# PX4FMUv2_3_SCH.net
KiCad netlist of a schematic drawn in Altium Designer
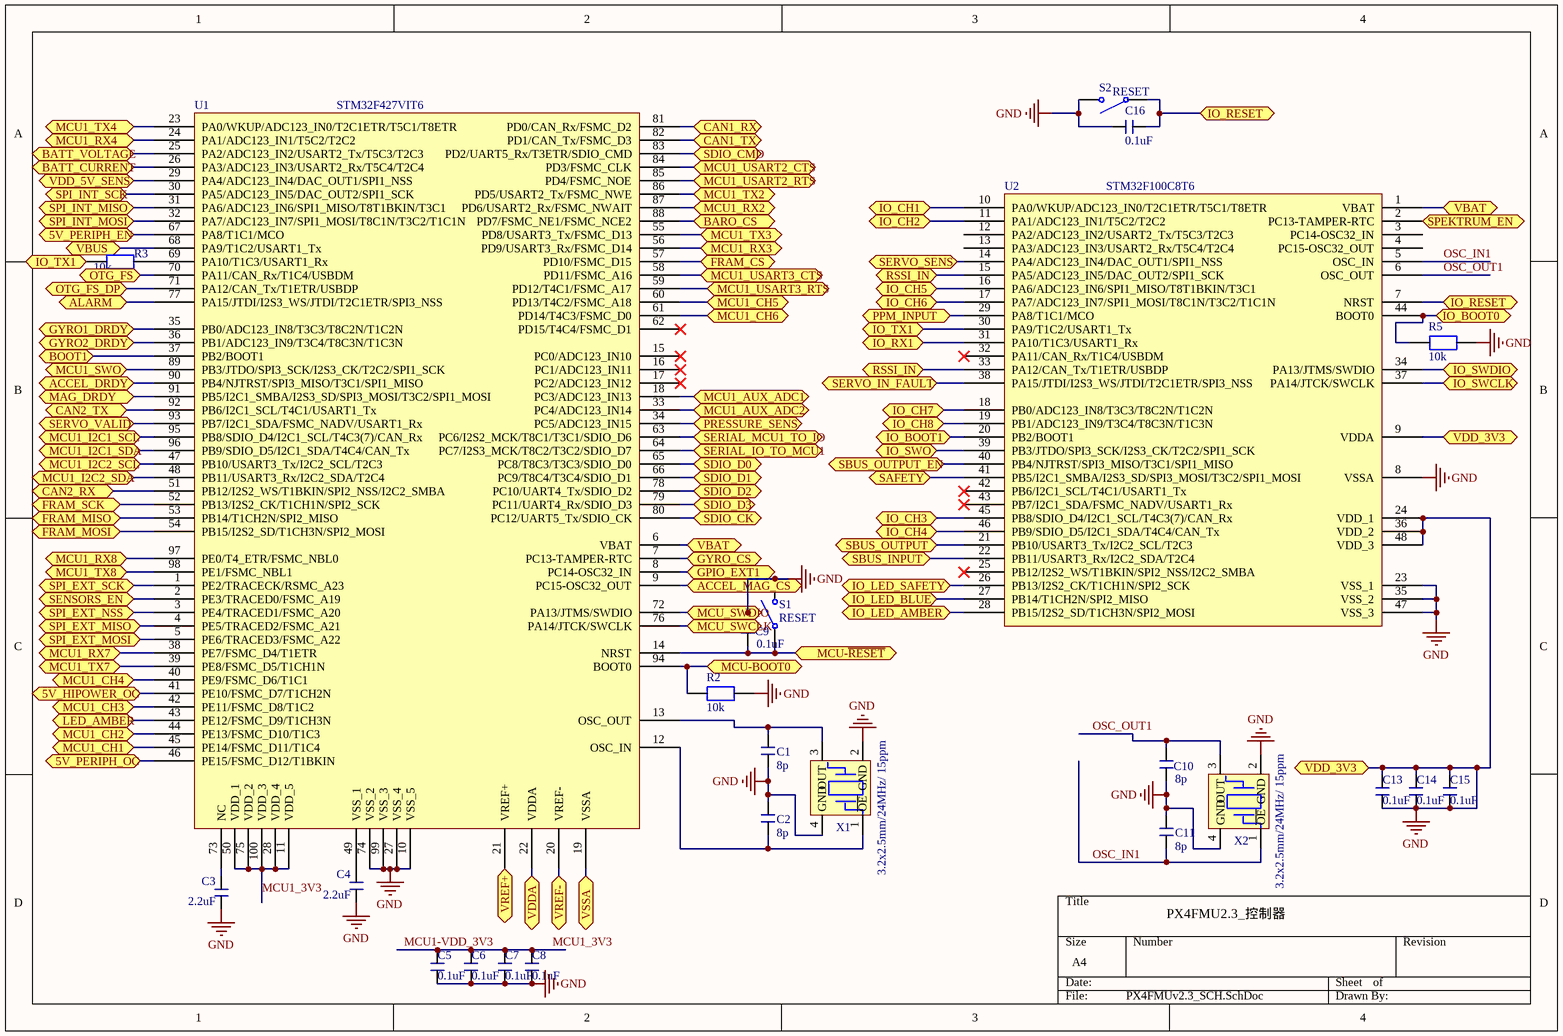
[diagram p0: PX4FMUv2.3_SCH.SchDoc]

(export (version "E")
  (design (tool "Eeschema 10.0.6"))
  (components
    (comp (ref "C1") (value "8p") (footprint "C 0402") (libsource (lib "px4_SCHLIB") (part "CAP_0402")))
    (comp (ref "C2") (value "8p") (footprint "C 0402") (libsource (lib "px4_SCHLIB") (part "CAP_0402")))
    (comp (ref "C3") (value "2.2uF") (footprint "C 0603_L") (libsource (lib "px4_SCHLIB") (part "CAP_0603")))
    (comp (ref "C4") (value "2.2uF") (footprint "C 0603_L") (libsource (lib "px4_SCHLIB") (part "CAP_0603")))
    (comp (ref "C5") (value "0.1uF") (footprint "C 0402") (libsource (lib "px4_SCHLIB") (part "CAP_0402")))
    (comp (ref "C6") (value "0.1uF") (footprint "C 0402") (libsource (lib "px4_SCHLIB") (part "CAP_0402")))
    (comp (ref "C7") (value "0.1uF") (footprint "C 0402") (libsource (lib "px4_SCHLIB") (part "CAP_0402")))
    (comp (ref "C8") (value "0.1uF") (footprint "C 0402") (libsource (lib "px4_SCHLIB") (part "CAP_0402")))
    (comp (ref "C9") (value "0.1uF") (footprint "C 0402") (libsource (lib "px4_SCHLIB") (part "CAP_0402")))
    (comp (ref "C10") (value "8p") (footprint "C 0402") (libsource (lib "px4_SCHLIB") (part "CAP_0402")))
    (comp (ref "C11") (value "8p") (footprint "C 0402") (libsource (lib "px4_SCHLIB") (part "CAP_0402")))
    (comp (ref "C13") (value "0.1uF") (footprint "C 0402") (libsource (lib "px4_SCHLIB") (part "CAP_0402")))
    (comp (ref "C14") (value "0.1uF") (footprint "C 0402") (libsource (lib "px4_SCHLIB") (part "CAP_0402")))
    (comp (ref "C15") (value "0.1uF") (footprint "C 0402") (libsource (lib "px4_SCHLIB") (part "CAP_0402")))
    (comp (ref "C16") (value "0.1uF") (footprint "C 0402") (libsource (lib "px4_SCHLIB") (part "CAP_0402")))
    (comp (ref "R2") (value "10k") (footprint "0402R") (libsource (lib "px4_SCHLIB") (part "Res_0402")))
    (comp (ref "R3") (value "10k") (footprint "0402R") (libsource (lib "px4_SCHLIB") (part "Res_0402")))
    (comp (ref "R5") (value "10k") (footprint "0402R") (libsource (lib "px4_SCHLIB") (part "Res_0402")))
    (comp (ref "S1")
      (value "RESET")
      (footprint "EVQP7J01K")
      (libsource (lib "px4_SCHLIB") (part "SWITCH-MOMENTARY-2"))
    )
    (comp (ref "S2")
      (value "RESET")
      (footprint "EVQP7J01K")
      (libsource (lib "px4_SCHLIB") (part "SWITCH-MOMENTARY-2"))
    )
    (comp (ref "U1")
      (value "STM32F427VIT6")
      (footprint "LQPF_100")
      (libsource (lib "px4_SCHLIB") (part "STM32F427VIT6"))
    )
    (comp (ref "U2")
      (value "STM32F100C8T6")
      (footprint "LQFP_48")
      (libsource (lib "px4_SCHLIB") (part "STM32F100C8T6"))
    )
    (comp (ref "X1")
      (value "3.2x2.5mm/24MHz/ 15ppm")
      (footprint "OSC 3225-4P")
      (libsource (lib "px4_SCHLIB") (part "OSCILLATOR"))
    )
    (comp (ref "X2")
      (value "3.2x2.5mm/24MHz/ 15ppm")
      (footprint "OSC 3225-4P")
      (libsource (lib "px4_SCHLIB") (part "OSCILLATOR"))
    )
  )
  (nets
    (net (code "1") (name "/5V_HIPOWER_OC") (class "Default")
      (node (ref "U1") (pin "41") (pinfunction "PE10/FSMC_D7/T1CH2N_41") (pintype "passive"))
    )
    (net (code "2") (name "/5V_PERIPH_EN") (class "Default")
      (node (ref "U1") (pin "67") (pinfunction "PA8/T1C1/MCO_67") (pintype "passive"))
    )
    (net (code "3") (name "/5V_PERIPH_OC") (class "Default")
      (node (ref "U1") (pin "46") (pinfunction "PE15/FSMC_D12/T1BKIN_46") (pintype "passive"))
    )
    (net (code "4") (name "/ACCEL_DRDY") (class "Default")
      (node (ref "U1") (pin "90") (pinfunction "PB4/NJTRST/SPI3_MISO/T3C1/SPI1_MISO_90") (pintype "passive"))
    )
    (net (code "5") (name "/ACCEL_MAG_CS") (class "Default")
      (node (ref "U1") (pin "9") (pinfunction "PC15-OSC32_OUT_9") (pintype "passive"))
    )
    (net (code "6") (name "/ALARM") (class "Default")
      (node (ref "U1") (pin "77") (pinfunction "PA15/JTDI/I2S3_WS/JTDI/T2C1ETR/SPI3_NSS_77") (pintype "passive"))
    )
    (net (code "7") (name "/BARO_CS") (class "Default")
      (node (ref "U1") (pin "88") (pinfunction "PD7/FSMC_NE1/FSMC_NCE2_88") (pintype "passive"))
    )
    (net (code "8") (name "/BATT_CURRENT") (class "Default")
      (node (ref "U1") (pin "26") (pinfunction "PA3/ADC123_IN3/USART2_Rx/T5C4/T2C4_26") (pintype "passive"))
    )
    (net (code "9") (name "/BATT_VOLTAGE") (class "Default")
      (node (ref "U1") (pin "25") (pinfunction "PA2/ADC123_IN2/USART2_Tx/T5C3/T2C3_25") (pintype "passive"))
    )
    (net (code "10") (name "/BOOT1") (class "Default")
      (node (ref "U1") (pin "37") (pinfunction "PB2/BOOT1_37") (pintype "passive"))
    )
    (net (code "11") (name "/CAN1_RX") (class "Default")
      (node (ref "U1") (pin "81") (pinfunction "PD0/CAN_Rx/FSMC_D2_81") (pintype "passive"))
    )
    (net (code "12") (name "/CAN1_TX") (class "Default")
      (node (ref "U1") (pin "82") (pinfunction "PD1/CAN_Tx/FSMC_D3_82") (pintype "passive"))
    )
    (net (code "13") (name "/CAN2_RX") (class "Default")
      (node (ref "U1") (pin "51") (pinfunction "PB12/I2S2_WS/T1BKIN/SPI2_NSS/I2C2_SMBA_51") (pintype "passive"))
    )
    (net (code "14") (name "/CAN2_TX") (class "Default")
      (node (ref "U1") (pin "92") (pinfunction "PB6/I2C1_SCL/T4C1/USART1_Tx_92") (pintype "passive"))
    )
    (net (code "15") (name "/FRAM_CS") (class "Default")
      (node (ref "U1") (pin "57") (pinfunction "PD10/FSMC_D15_57") (pintype "passive"))
    )
    (net (code "16") (name "/FRAM_MISO") (class "Default")
      (node (ref "U1") (pin "53") (pinfunction "PB14/T1CH2N/SPI2_MISO_53") (pintype "passive"))
    )
    (net (code "17") (name "/FRAM_MOSI") (class "Default")
      (node (ref "U1") (pin "54") (pinfunction "PB15/I2S2_SD/T1CH3N/SPI2_MOSI_54") (pintype "passive"))
    )
    (net (code "18") (name "/FRAM_SCK") (class "Default")
      (node (ref "U1") (pin "52") (pinfunction "PB13/I2S2_CK/T1CH1N/SPI2_SCK_52") (pintype "passive"))
    )
    (net (code "19") (name "/GPIO_EXT1") (class "Default")
      (node (ref "U1") (pin "8") (pinfunction "PC14-OSC32_IN_8") (pintype "passive"))
    )
    (net (code "20") (name "/GYRO1_DRDY") (class "Default")
      (node (ref "U1") (pin "35") (pinfunction "PB0/ADC123_IN8/T3C3/T8C2N/T1C2N_35") (pintype "passive"))
    )
    (net (code "21") (name "/GYRO2_DRDY") (class "Default")
      (node (ref "U1") (pin "36") (pinfunction "PB1/ADC123_IN9/T3C4/T8C3N/T1C3N_36") (pintype "passive"))
    )
    (net (code "22") (name "/GYRO_CS") (class "Default")
      (node (ref "U1") (pin "7") (pinfunction "PC13-TAMPER-RTC_7") (pintype "passive"))
    )
    (net (code "23") (name "/IO_BOOT0") (class "Default")
      (node (ref "R5") (pin "2") (pinfunction "2_2") (pintype "passive"))
      (node (ref "U2") (pin "44") (pinfunction "BOOT0_44") (pintype "passive"))
    )
    (net (code "24") (name "/IO_BOOT1") (class "Default")
      (node (ref "U2") (pin "20") (pinfunction "PB2/BOOT1_20") (pintype "passive"))
    )
    (net (code "25") (name "/IO_CH1") (class "Default")
      (node (ref "U2") (pin "10") (pinfunction "PA0/WKUP/ADC123_IN0/T2C1ETR/T5C1/T8ETR_10") (pintype "passive"))
    )
    (net (code "26") (name "/IO_CH2") (class "Default")
      (node (ref "U2") (pin "11") (pinfunction "PA1/ADC123_IN1/T5C2/T2C2_11") (pintype "passive"))
    )
    (net (code "27") (name "/IO_CH3") (class "Default")
      (node (ref "U2") (pin "45") (pinfunction "PB8/SDIO_D4/I2C1_SCL/T4C3(7)/CAN_Rx_45") (pintype "passive"))
    )
    (net (code "28") (name "/IO_CH4") (class "Default")
      (node (ref "U2") (pin "46") (pinfunction "PB9/SDIO_D5/I2C1_SDA/T4C4/CAN_Tx_46") (pintype "passive"))
    )
    (net (code "29") (name "/IO_CH5") (class "Default")
      (node (ref "U2") (pin "16") (pinfunction "PA6/ADC123_IN6/SPI1_MISO/T8T1BKIN/T3C1_16") (pintype "passive"))
    )
    (net (code "30") (name "/IO_CH6") (class "Default")
      (node (ref "U2") (pin "17") (pinfunction "PA7/ADC123_IN7/SPI1_MOSI/T8C1N/T3C2/T1C1N_17") (pintype "passive"))
    )
    (net (code "31") (name "/IO_CH7") (class "Default")
      (node (ref "U2") (pin "18") (pinfunction "PB0/ADC123_IN8/T3C3/T8C2N/T1C2N_18") (pintype "passive"))
    )
    (net (code "32") (name "/IO_CH8") (class "Default")
      (node (ref "U2") (pin "19") (pinfunction "PB1/ADC123_IN9/T3C4/T8C3N/T1C3N_19") (pintype "passive"))
    )
    (net (code "33") (name "/IO_LED_AMBER") (class "Default")
      (node (ref "U2") (pin "28") (pinfunction "PB15/I2S2_SD/T1CH3N/SPI2_MOSI_28") (pintype "passive"))
    )
    (net (code "34") (name "/IO_LED_BLUE") (class "Default")
      (node (ref "U2") (pin "27") (pinfunction "PB14/T1CH2N/SPI2_MISO_27") (pintype "passive"))
    )
    (net (code "35") (name "/IO_LED_SAFETY") (class "Default")
      (node (ref "U2") (pin "26") (pinfunction "PB13/I2S2_CK/T1CH1N/SPI2_SCK_26") (pintype "passive"))
    )
    (net (code "36") (name "/IO_RESET") (class "Default")
      (node (ref "C16") (pin "1") (pinfunction "1_1") (pintype "passive"))
      (node (ref "S2") (pin "1") (pinfunction "1_1") (pintype "passive"))
      (node (ref "U2") (pin "7") (pinfunction "NRST_7") (pintype "passive"))
    )
    (net (code "37") (name "/IO_RX1") (class "Default")
      (node (ref "U2") (pin "31") (pinfunction "PA10/T1C3/USART1_Rx_31") (pintype "passive"))
    )
    (net (code "38") (name "/IO_SWCLK") (class "Default")
      (node (ref "U2") (pin "37") (pinfunction "PA14/JTCK/SWCLK_37") (pintype "passive"))
    )
    (net (code "39") (name "/IO_SWDIO") (class "Default")
      (node (ref "U2") (pin "34") (pinfunction "PA13/JTMS/SWDIO_34") (pintype "passive"))
    )
    (net (code "40") (name "/IO_SWO") (class "Default")
      (node (ref "U2") (pin "39") (pinfunction "PB3/JTDO/SPI3_SCK/I2S3_CK/T2C2/SPI1_SCK_39") (pintype "passive"))
    )
    (net (code "41") (name "/IO_TX1") (class "Default")
      (node (ref "R3") (pin "1") (pinfunction "1_1") (pintype "passive"))
      (node (ref "U2") (pin "30") (pinfunction "PA9/T1C2/USART1_Tx_30") (pintype "passive"))
    )
    (net (code "42") (name "/LED_AMBER") (class "Default")
      (node (ref "U1") (pin "43") (pinfunction "PE12/FSMC_D9/T1CH3N_43") (pintype "passive"))
    )
    (net (code "43") (name "/MAG_DRDY") (class "Default")
      (node (ref "U1") (pin "91") (pinfunction "PB5/I2C1_SMBA/I2S3_SD/SPI3_MOSI/T3C2/SPI1_MOSI_91") (pintype "passive"))
    )
    (net (code "44") (name "/MCU-BOOT0") (class "Default")
      (node (ref "R2") (pin "2") (pinfunction "2_2") (pintype "passive"))
      (node (ref "U1") (pin "94") (pinfunction "BOOT0_94") (pintype "passive"))
    )
    (net (code "45") (name "/MCU-~{RESET}") (class "Default")
      (node (ref "C9") (pin "1") (pinfunction "1_1") (pintype "passive"))
      (node (ref "S1") (pin "1") (pinfunction "1_1") (pintype "passive"))
      (node (ref "U1") (pin "14") (pinfunction "NRST_14") (pintype "passive"))
    )
    (net (code "46") (name "/MCU1-VDD_3V3") (class "Default")
      (node (ref "C5") (pin "1") (pinfunction "1_1") (pintype "passive"))
      (node (ref "C6") (pin "1") (pinfunction "1_1") (pintype "passive"))
      (node (ref "C7") (pin "1") (pinfunction "1_1") (pintype "passive"))
      (node (ref "C8") (pin "1") (pinfunction "1_1") (pintype "passive"))
      (node (ref "U1") (pin "100") (pinfunction "VDD_3_100") (pintype "passive"))
      (node (ref "U1") (pin "11") (pinfunction "VDD_5_11") (pintype "passive"))
      (node (ref "U1") (pin "28") (pinfunction "VDD_4_28") (pintype "passive"))
      (node (ref "U1") (pin "50") (pinfunction "VDD_1_50") (pintype "passive"))
      (node (ref "U1") (pin "75") (pinfunction "VDD_2_75") (pintype "passive"))
    )
    (net (code "47") (name "/MCU1_AUX_ADC1") (class "Default")
      (node (ref "U1") (pin "18") (pinfunction "PC3/ADC123_IN13_18") (pintype "passive"))
    )
    (net (code "48") (name "/MCU1_AUX_ADC2") (class "Default")
      (node (ref "U1") (pin "33") (pinfunction "PC4/ADC123_IN14_33") (pintype "passive"))
    )
    (net (code "49") (name "/MCU1_CH1") (class "Default")
      (node (ref "U1") (pin "45") (pinfunction "PE14/FSMC_D11/T1C4_45") (pintype "passive"))
    )
    (net (code "50") (name "/MCU1_CH2") (class "Default")
      (node (ref "U1") (pin "44") (pinfunction "PE13/FSMC_D10/T1C3_44") (pintype "passive"))
    )
    (net (code "51") (name "/MCU1_CH3") (class "Default")
      (node (ref "U1") (pin "42") (pinfunction "PE11/FSMC_D8/T1C2_42") (pintype "passive"))
    )
    (net (code "52") (name "/MCU1_CH4") (class "Default")
      (node (ref "U1") (pin "40") (pinfunction "PE9/FSMC_D6/T1C1_40") (pintype "passive"))
    )
    (net (code "53") (name "/MCU1_CH5") (class "Default")
      (node (ref "U1") (pin "60") (pinfunction "PD13/T4C2/FSMC_A18_60") (pintype "passive"))
    )
    (net (code "54") (name "/MCU1_CH6") (class "Default")
      (node (ref "U1") (pin "61") (pinfunction "PD14/T4C3/FSMC_D0_61") (pintype "passive"))
    )
    (net (code "55") (name "/MCU1_I2C1_SCL") (class "Default")
      (node (ref "U1") (pin "95") (pinfunction "PB8/SDIO_D4/I2C1_SCL/T4C3(7)/CAN_Rx_95") (pintype "passive"))
    )
    (net (code "56") (name "/MCU1_I2C1_SDA") (class "Default")
      (node (ref "U1") (pin "96") (pinfunction "PB9/SDIO_D5/I2C1_SDA/T4C4/CAN_Tx_96") (pintype "passive"))
    )
    (net (code "57") (name "/MCU1_I2C2_SCL") (class "Default")
      (node (ref "U1") (pin "47") (pinfunction "PB10/USART3_Tx/I2C2_SCL/T2C3_47") (pintype "passive"))
    )
    (net (code "58") (name "/MCU1_I2C2_SDA") (class "Default")
      (node (ref "U1") (pin "48") (pinfunction "PB11/USART3_Rx/I2C2_SDA/T2C4_48") (pintype "passive"))
    )
    (net (code "59") (name "/MCU1_RX2") (class "Default")
      (node (ref "U1") (pin "87") (pinfunction "PD6/USART2_Rx/FSMC_NWAIT_87") (pintype "passive"))
    )
    (net (code "60") (name "/MCU1_RX3") (class "Default")
      (node (ref "U1") (pin "56") (pinfunction "PD9/USART3_Rx/FSMC_D14_56") (pintype "passive"))
    )
    (net (code "61") (name "/MCU1_RX4") (class "Default")
      (node (ref "U1") (pin "24") (pinfunction "PA1/ADC123_IN1/T5C2/T2C2_24") (pintype "passive"))
    )
    (net (code "62") (name "/MCU1_RX7") (class "Default")
      (node (ref "U1") (pin "38") (pinfunction "PE7/FSMC_D4/T1ETR_38") (pintype "passive"))
    )
    (net (code "63") (name "/MCU1_RX8") (class "Default")
      (node (ref "U1") (pin "97") (pinfunction "PE0/T4_ETR/FSMC_NBL0_97") (pintype "passive"))
    )
    (net (code "64") (name "/MCU1_SWO") (class "Default")
      (node (ref "U1") (pin "89") (pinfunction "PB3/JTDO/SPI3_SCK/I2S3_CK/T2C2/SPI1_SCK_89") (pintype "passive"))
    )
    (net (code "65") (name "/MCU1_TX2") (class "Default")
      (node (ref "U1") (pin "86") (pinfunction "PD5/USART2_Tx/FSMC_NWE_86") (pintype "passive"))
    )
    (net (code "66") (name "/MCU1_TX3") (class "Default")
      (node (ref "U1") (pin "55") (pinfunction "PD8/USART3_Tx/FSMC_D13_55") (pintype "passive"))
    )
    (net (code "67") (name "/MCU1_TX4") (class "Default")
      (node (ref "U1") (pin "23") (pinfunction "PA0/WKUP/ADC123_IN0/T2C1ETR/T5C1/T8ETR_23") (pintype "passive"))
    )
    (net (code "68") (name "/MCU1_TX7") (class "Default")
      (node (ref "U1") (pin "39") (pinfunction "PE8/FSMC_D5/T1CH1N_39") (pintype "passive"))
    )
    (net (code "69") (name "/MCU1_TX8") (class "Default")
      (node (ref "U1") (pin "98") (pinfunction "PE1/FSMC_NBL1_98") (pintype "passive"))
    )
    (net (code "70") (name "/MCU1_USART2_CTS") (class "Default")
      (node (ref "U1") (pin "84") (pinfunction "PD3/FSMC_CLK_84") (pintype "passive"))
    )
    (net (code "71") (name "/MCU1_USART2_RTS") (class "Default")
      (node (ref "U1") (pin "85") (pinfunction "PD4/FSMC_NOE_85") (pintype "passive"))
    )
    (net (code "72") (name "/MCU1_USART3_CTS") (class "Default")
      (node (ref "U1") (pin "58") (pinfunction "PD11/FSMC_A16_58") (pintype "passive"))
    )
    (net (code "73") (name "/MCU1_USART3_RTS") (class "Default")
      (node (ref "U1") (pin "59") (pinfunction "PD12/T4C1/FSMC_A17_59") (pintype "passive"))
    )
    (net (code "74") (name "/MCU_SWCLK") (class "Default")
      (node (ref "U1") (pin "76") (pinfunction "PA14/JTCK/SWCLK_76") (pintype "passive"))
    )
    (net (code "75") (name "/MCU_SWDIO") (class "Default")
      (node (ref "U1") (pin "72") (pinfunction "PA13/JTMS/SWDIO_72") (pintype "passive"))
    )
    (net (code "76") (name "/OSC_IN1") (class "Default")
      (node (ref "C11") (pin "2") (pinfunction "2_2") (pintype "passive"))
      (node (ref "U2") (pin "5") (pinfunction "OSC_IN_5") (pintype "passive"))
      (node (ref "X2") (pin "1") (pinfunction "OE_1") (pintype "passive"))
    )
    (net (code "77") (name "/OSC_OUT1") (class "Default")
      (node (ref "C10") (pin "1") (pinfunction "1_1") (pintype "passive"))
      (node (ref "U2") (pin "6") (pinfunction "OSC_OUT_6") (pintype "passive"))
      (node (ref "X2") (pin "3") (pinfunction "OUT_3") (pintype "passive"))
    )
    (net (code "78") (name "/OTG_FS") (class "Default")
      (node (ref "U1") (pin "70") (pinfunction "PA11/CAN_Rx/T1C4/USBDM_70") (pintype "passive"))
    )
    (net (code "79") (name "/OTG_FS_DP") (class "Default")
      (node (ref "U1") (pin "71") (pinfunction "PA12/CAN_Tx/T1ETR/USBDP_71") (pintype "passive"))
    )
    (net (code "80") (name "/PPM_INPUT") (class "Default")
      (node (ref "U2") (pin "29") (pinfunction "PA8/T1C1/MCO_29") (pintype "passive"))
    )
    (net (code "81") (name "/PRESSURE_SENS") (class "Default")
      (node (ref "U1") (pin "34") (pinfunction "PC5/ADC123_IN15_34") (pintype "passive"))
    )
    (net (code "82") (name "/RSSI_IN") (class "Default")
      (node (ref "U2") (pin "15") (pinfunction "PA5/ADC123_IN5/DAC_OUT2/SPI1_SCK_15") (pintype "passive"))
      (node (ref "U2") (pin "33") (pinfunction "PA12/CAN_Tx/T1ETR/USBDP_33") (pintype "passive"))
    )
    (net (code "83") (name "/SAFETY") (class "Default")
      (node (ref "U2") (pin "41") (pinfunction "PB5/I2C1_SMBA/I2S3_SD/SPI3_MOSI/T3C2/SPI1_MOSI_41") (pintype "passive"))
    )
    (net (code "84") (name "/SBUS_INPUT") (class "Default")
      (node (ref "U2") (pin "22") (pinfunction "PB11/USART3_Rx/I2C2_SDA/T2C4_22") (pintype "passive"))
    )
    (net (code "85") (name "/SBUS_OUTPUT") (class "Default")
      (node (ref "U2") (pin "21") (pinfunction "PB10/USART3_Tx/I2C2_SCL/T2C3_21") (pintype "passive"))
    )
    (net (code "86") (name "/SBUS_OUTPUT_EN") (class "Default")
      (node (ref "U2") (pin "40") (pinfunction "PB4/NJTRST/SPI3_MISO/T3C1/SPI1_MISO_40") (pintype "passive"))
    )
    (net (code "87") (name "/SDIO_CK") (class "Default")
      (node (ref "U1") (pin "80") (pinfunction "PC12/UART5_Tx/SDIO_CK_80") (pintype "passive"))
    )
    (net (code "88") (name "/SDIO_CMD") (class "Default")
      (node (ref "U1") (pin "83") (pinfunction "PD2/UART5_Rx/T3ETR/SDIO_CMD_83") (pintype "passive"))
    )
    (net (code "89") (name "/SDIO_D0") (class "Default")
      (node (ref "U1") (pin "65") (pinfunction "PC8/T8C3/T3C3/SDIO_D0_65") (pintype "passive"))
    )
    (net (code "90") (name "/SDIO_D1") (class "Default")
      (node (ref "U1") (pin "66") (pinfunction "PC9/T8C4/T3C4/SDIO_D1_66") (pintype "passive"))
    )
    (net (code "91") (name "/SDIO_D2") (class "Default")
      (node (ref "U1") (pin "78") (pinfunction "PC10/UART4_Tx/SDIO_D2_78") (pintype "passive"))
    )
    (net (code "92") (name "/SDIO_D3") (class "Default")
      (node (ref "U1") (pin "79") (pinfunction "PC11/UART4_Rx/SDIO_D3_79") (pintype "passive"))
    )
    (net (code "93") (name "/SENSORS_EN") (class "Default")
      (node (ref "U1") (pin "2") (pinfunction "PE3/TRACED0/FSMC_A19_2") (pintype "passive"))
    )
    (net (code "94") (name "/SERIAL_IO_TO_MCU1") (class "Default")
      (node (ref "U1") (pin "64") (pinfunction "PC7/I2S3_MCK/T8C2/T3C2/SDIO_D7_64") (pintype "passive"))
    )
    (net (code "95") (name "/SERIAL_MCU1_TO_IO") (class "Default")
      (node (ref "U1") (pin "63") (pinfunction "PC6/I2S2_MCK/T8C1/T3C1/SDIO_D6_63") (pintype "passive"))
    )
    (net (code "96") (name "/SERVO_IN_FAULT") (class "Default")
      (node (ref "U2") (pin "38") (pinfunction "PA15/JTDI/I2S3_WS/JTDI/T2C1ETR/SPI3_NSS_38") (pintype "passive"))
    )
    (net (code "97") (name "/SERVO_SENS") (class "Default")
      (node (ref "U2") (pin "14") (pinfunction "PA4/ADC123_IN4/DAC_OUT1/SPI1_NSS_14") (pintype "passive"))
    )
    (net (code "98") (name "/SERVO_VALID") (class "Default")
      (node (ref "U1") (pin "93") (pinfunction "PB7/I2C1_SDA/FSMC_NADV/USART1_Rx_93") (pintype "passive"))
    )
    (net (code "99") (name "/SPEKTRUM_EN") (class "Default")
      (node (ref "U2") (pin "2") (pinfunction "PC13-TAMPER-RTC_2") (pintype "passive"))
    )
    (net (code "100") (name "/SPI_EXT_MISO") (class "Default")
      (node (ref "U1") (pin "4") (pinfunction "PE5/TRACED2/FSMC_A21_4") (pintype "passive"))
    )
    (net (code "101") (name "/SPI_EXT_MOSI") (class "Default")
      (node (ref "U1") (pin "5") (pinfunction "PE6/TRACED3/FSMC_A22_5") (pintype "passive"))
    )
    (net (code "102") (name "/SPI_EXT_NSS") (class "Default")
      (node (ref "U1") (pin "3") (pinfunction "PE4/TRACED1/FSMC_A20_3") (pintype "passive"))
    )
    (net (code "103") (name "/SPI_EXT_SCK") (class "Default")
      (node (ref "U1") (pin "1") (pinfunction "PE2/TRACECK/RSMC_A23_1") (pintype "passive"))
    )
    (net (code "104") (name "/SPI_INT_MISO") (class "Default")
      (node (ref "U1") (pin "31") (pinfunction "PA6/ADC123_IN6/SPI1_MISO/T8T1BKIN/T3C1_31") (pintype "passive"))
    )
    (net (code "105") (name "/SPI_INT_MOSI") (class "Default")
      (node (ref "U1") (pin "32") (pinfunction "PA7/ADC123_IN7/SPI1_MOSI/T8C1N/T3C2/T1C1N_32") (pintype "passive"))
    )
    (net (code "106") (name "/SPI_INT_SCK") (class "Default")
      (node (ref "U1") (pin "30") (pinfunction "PA5/ADC123_IN5/DAC_OUT2/SPI1_SCK_30") (pintype "passive"))
    )
    (net (code "107") (name "/VBAT") (class "Default")
      (node (ref "U1") (pin "6") (pinfunction "VBAT_6") (pintype "passive"))
      (node (ref "U2") (pin "1") (pinfunction "VBAT_1") (pintype "passive"))
    )
    (net (code "108") (name "/VBUS") (class "Default")
      (node (ref "U1") (pin "68") (pinfunction "PA9/T1C2/USART1_Tx_68") (pintype "passive"))
    )
    (net (code "109") (name "/VDDA") (class "Default")
      (node (ref "U1") (pin "22") (pinfunction "VDDA_22") (pintype "passive"))
    )
    (net (code "110") (name "/VDD_5V_SENS") (class "Default")
      (node (ref "U1") (pin "29") (pinfunction "PA4/ADC123_IN4/DAC_OUT1/SPI1_NSS_29") (pintype "passive"))
    )
    (net (code "111") (name "/VREF+") (class "Default")
      (node (ref "U1") (pin "21") (pinfunction "VREF+_21") (pintype "passive"))
    )
    (net (code "112") (name "/VREF-") (class "Default")
      (node (ref "U1") (pin "20") (pinfunction "VREF-_20") (pintype "passive"))
    )
    (net (code "113") (name "/VSSA") (class "Default")
      (node (ref "U1") (pin "19") (pinfunction "VSSA_19") (pintype "passive"))
    )
    (net (code "114") (name "GND") (class "Default")
      (node (ref "C1") (pin "2") (pinfunction "2_2") (pintype "passive"))
      (node (ref "C10") (pin "2") (pinfunction "2_2") (pintype "passive"))
      (node (ref "C11") (pin "1") (pinfunction "1_1") (pintype "passive"))
      (node (ref "C13") (pin "1") (pinfunction "1_1") (pintype "passive"))
      (node (ref "C13") (pin "2") (pinfunction "2_2") (pintype "passive"))
      (node (ref "C14") (pin "1") (pinfunction "1_1") (pintype "passive"))
      (node (ref "C14") (pin "2") (pinfunction "2_2") (pintype "passive"))
      (node (ref "C15") (pin "1") (pinfunction "1_1") (pintype "passive"))
      (node (ref "C15") (pin "2") (pinfunction "2_2") (pintype "passive"))
      (node (ref "C16") (pin "2") (pinfunction "2_2") (pintype "passive"))
      (node (ref "C2") (pin "1") (pinfunction "1_1") (pintype "passive"))
      (node (ref "C3") (pin "2") (pinfunction "2_2") (pintype "passive"))
      (node (ref "C4") (pin "2") (pinfunction "2_2") (pintype "passive"))
      (node (ref "C5") (pin "2") (pinfunction "2_2") (pintype "passive"))
      (node (ref "C6") (pin "2") (pinfunction "2_2") (pintype "passive"))
      (node (ref "C7") (pin "2") (pinfunction "2_2") (pintype "passive"))
      (node (ref "C8") (pin "2") (pinfunction "2_2") (pintype "passive"))
      (node (ref "C9") (pin "2") (pinfunction "2_2") (pintype "passive"))
      (node (ref "R2") (pin "1") (pinfunction "1_1") (pintype "passive"))
      (node (ref "R5") (pin "1") (pinfunction "1_1") (pintype "passive"))
      (node (ref "S1") (pin "2") (pinfunction "2_2") (pintype "passive"))
      (node (ref "S2") (pin "2") (pinfunction "2_2") (pintype "passive"))
      (node (ref "U1") (pin "10") (pinfunction "VSS_5_10") (pintype "passive"))
      (node (ref "U1") (pin "27") (pinfunction "VSS_4_27") (pintype "passive"))
      (node (ref "U1") (pin "74") (pinfunction "VSS_2_74") (pintype "passive"))
      (node (ref "U1") (pin "99") (pinfunction "VSS_3_99") (pintype "passive"))
      (node (ref "U2") (pin "23") (pinfunction "VSS_1_23") (pintype "passive"))
      (node (ref "U2") (pin "24") (pinfunction "VDD_1_24") (pintype "passive"))
      (node (ref "U2") (pin "35") (pinfunction "VSS_2_35") (pintype "passive"))
      (node (ref "U2") (pin "36") (pinfunction "VDD_2_36") (pintype "passive"))
      (node (ref "U2") (pin "47") (pinfunction "VSS_3_47") (pintype "passive"))
      (node (ref "U2") (pin "48") (pinfunction "VDD_3_48") (pintype "passive"))
      (node (ref "U2") (pin "8") (pinfunction "VSSA_8") (pintype "passive"))
      (node (ref "U2") (pin "9") (pinfunction "VDDA_9") (pintype "passive"))
      (node (ref "X1") (pin "2") (pinfunction "GND_2") (pintype "passive"))
      (node (ref "X1") (pin "4") (pinfunction "GND_4") (pintype "passive"))
      (node (ref "X2") (pin "2") (pinfunction "GND_2") (pintype "passive"))
      (node (ref "X2") (pin "4") (pinfunction "GND_4") (pintype "passive"))
    )
    (net (code "115") (name "Net-(U1-NC)") (class "Default")
      (node (ref "C3") (pin "1") (pinfunction "1_1") (pintype "passive"))
      (node (ref "U1") (pin "73") (pinfunction "NC_73") (pintype "passive"))
    )
    (net (code "116") (name "Net-(U1-OSC_IN)") (class "Default")
      (node (ref "C2") (pin "2") (pinfunction "2_2") (pintype "passive"))
      (node (ref "U1") (pin "12") (pinfunction "OSC_IN_12") (pintype "passive"))
      (node (ref "X1") (pin "1") (pinfunction "OE_1") (pintype "passive"))
    )
    (net (code "117") (name "Net-(U1-OSC_OUT)") (class "Default")
      (node (ref "C1") (pin "1") (pinfunction "1_1") (pintype "passive"))
      (node (ref "U1") (pin "13") (pinfunction "OSC_OUT_13") (pintype "passive"))
      (node (ref "X1") (pin "3") (pinfunction "OUT_3") (pintype "passive"))
    )
    (net (code "118") (name "Net-(U1-PA10{slash}T1C3{slash}USART1_Rx)") (class "Default")
      (node (ref "R3") (pin "2") (pinfunction "2_2") (pintype "passive"))
      (node (ref "U1") (pin "69") (pinfunction "PA10/T1C3/USART1_Rx_69") (pintype "passive"))
    )
    (net (code "119") (name "Net-(U1-VSS_1)") (class "Default")
      (node (ref "C4") (pin "1") (pinfunction "1_1") (pintype "passive"))
      (node (ref "U1") (pin "49") (pinfunction "VSS_1_49") (pintype "passive"))
    )
    (net (code "120") (name "unconnected-(U1-PC0{slash}ADC123_IN10-Pad15)") (class "Default")
      (node (ref "U1") (pin "15") (pinfunction "PC0/ADC123_IN10_15") (pintype "passive+no_connect"))
    )
    (net (code "121") (name "unconnected-(U1-PC1{slash}ADC123_IN11-Pad16)") (class "Default")
      (node (ref "U1") (pin "16") (pinfunction "PC1/ADC123_IN11_16") (pintype "passive+no_connect"))
    )
    (net (code "122") (name "unconnected-(U1-PC2{slash}ADC123_IN12-Pad17)") (class "Default")
      (node (ref "U1") (pin "17") (pinfunction "PC2/ADC123_IN12_17") (pintype "passive+no_connect"))
    )
    (net (code "123") (name "unconnected-(U1-PD15{slash}T4C4{slash}FSMC_D1-Pad62)") (class "Default")
      (node (ref "U1") (pin "62") (pinfunction "PD15/T4C4/FSMC_D1_62") (pintype "passive+no_connect"))
    )
    (net (code "124") (name "unconnected-(U2-PA2{slash}ADC123_IN2{slash}USART2_Tx{slash}T5C3{slash}T2C3-Pad12)") (class "Default")
      (node (ref "U2") (pin "12") (pinfunction "PA2/ADC123_IN2/USART2_Tx/T5C3/T2C3_12") (pintype "passive"))
    )
    (net (code "125") (name "unconnected-(U2-PA3{slash}ADC123_IN3{slash}USART2_Rx{slash}T5C4{slash}T2C4-Pad13)") (class "Default")
      (node (ref "U2") (pin "13") (pinfunction "PA3/ADC123_IN3/USART2_Rx/T5C4/T2C4_13") (pintype "passive"))
    )
    (net (code "126") (name "unconnected-(U2-PA11{slash}CAN_Rx{slash}T1C4{slash}USBDM-Pad32)") (class "Default")
      (node (ref "U2") (pin "32") (pinfunction "PA11/CAN_Rx/T1C4/USBDM_32") (pintype "passive+no_connect"))
    )
    (net (code "127") (name "unconnected-(U2-PB6{slash}I2C1_SCL{slash}T4C1{slash}USART1_Tx-Pad42)") (class "Default")
      (node (ref "U2") (pin "42") (pinfunction "PB6/I2C1_SCL/T4C1/USART1_Tx_42") (pintype "passive+no_connect"))
    )
    (net (code "128") (name "unconnected-(U2-PB7{slash}I2C1_SDA{slash}FSMC_NADV{slash}USART1_Rx-Pad43)") (class "Default")
      (node (ref "U2") (pin "43") (pinfunction "PB7/I2C1_SDA/FSMC_NADV/USART1_Rx_43") (pintype "passive+no_connect"))
    )
    (net (code "129") (name "unconnected-(U2-PB12{slash}I2S2_WS{slash}T1BKIN{slash}SPI2_NSS{slash}I2C2_SMBA-Pad25)") (class "Default")
      (node (ref "U2") (pin "25") (pinfunction "PB12/I2S2_WS/T1BKIN/SPI2_NSS/I2C2_SMBA_25") (pintype "passive+no_connect"))
    )
    (net (code "130") (name "unconnected-(U2-PC14-OSC32_IN-Pad3)") (class "Default")
      (node (ref "U2") (pin "3") (pinfunction "PC14-OSC32_IN_3") (pintype "passive"))
    )
    (net (code "131") (name "unconnected-(U2-PC15-OSC32_OUT-Pad4)") (class "Default")
      (node (ref "U2") (pin "4") (pinfunction "PC15-OSC32_OUT_4") (pintype "passive"))
    )
  )
)
